# Flex_design.net
KiCad netlist of a schematic drawn in Altium Designer
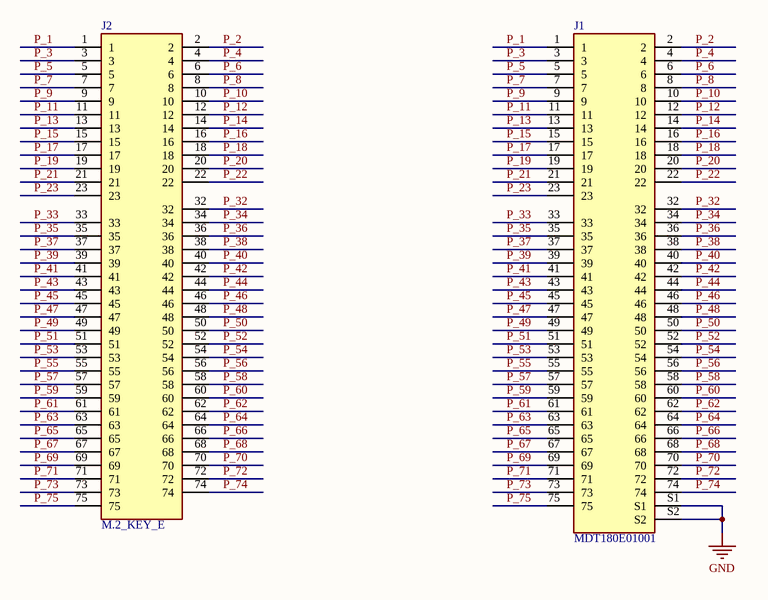
[diagram p0: Flex_design.SchDoc]

(export (version "E")
  (design (tool "Eeschema 10.0.6"))
  (components
    (comp (ref "J1")
      (value "MDT180E01001")
      (footprint "AMPHENOL_MDT180E01001")
      (description "PCIe M.2 Connectors, Storage and Server Connector, P=0.5mm, H=1.8mm, Key E, 30渭in Au Plating")
      (fields (field (name "MF") "Amphenol"))
      (libsource (lib "flex_Sch") (part "MDT180E01001"))
    )
    (comp (ref "J2")
      (value "M.2_KEY_E")
      (footprint "M.2_KEY_E")
      (libsource (lib "flex_Sch") (part "M.2_KEY_E"))
    )
  )
  (nets
    (net (code "1") (name "/P_1") (class "Default")
      (node (ref "J1") (pin "1") (pinfunction "1_1") (pintype "passive"))
      (node (ref "J2") (pin "1") (pinfunction "1_1") (pintype "passive"))
    )
    (net (code "2") (name "/P_2") (class "Default")
      (node (ref "J1") (pin "2") (pinfunction "2_2") (pintype "passive"))
      (node (ref "J2") (pin "2") (pinfunction "2_2") (pintype "passive"))
    )
    (net (code "3") (name "/P_3") (class "Default")
      (node (ref "J1") (pin "3") (pinfunction "3_3") (pintype "passive"))
      (node (ref "J2") (pin "3") (pinfunction "3_3") (pintype "passive"))
    )
    (net (code "4") (name "/P_4") (class "Default")
      (node (ref "J1") (pin "4") (pinfunction "4_4") (pintype "passive"))
      (node (ref "J2") (pin "4") (pinfunction "4_4") (pintype "passive"))
    )
    (net (code "5") (name "/P_5") (class "Default")
      (node (ref "J1") (pin "5") (pinfunction "5_5") (pintype "passive"))
      (node (ref "J2") (pin "5") (pinfunction "5_5") (pintype "passive"))
    )
    (net (code "6") (name "/P_6") (class "Default")
      (node (ref "J1") (pin "6") (pinfunction "6_6") (pintype "passive"))
      (node (ref "J2") (pin "6") (pinfunction "6_6") (pintype "passive"))
    )
    (net (code "7") (name "/P_7") (class "Default")
      (node (ref "J1") (pin "7") (pinfunction "7_7") (pintype "passive"))
      (node (ref "J2") (pin "7") (pinfunction "7_7") (pintype "passive"))
    )
    (net (code "8") (name "/P_8") (class "Default")
      (node (ref "J1") (pin "8") (pinfunction "8_8") (pintype "passive"))
      (node (ref "J2") (pin "8") (pinfunction "8_8") (pintype "passive"))
    )
    (net (code "9") (name "/P_9") (class "Default")
      (node (ref "J1") (pin "9") (pinfunction "9_9") (pintype "passive"))
      (node (ref "J2") (pin "9") (pinfunction "9_9") (pintype "passive"))
    )
    (net (code "10") (name "/P_10") (class "Default")
      (node (ref "J1") (pin "10") (pinfunction "10_10") (pintype "passive"))
      (node (ref "J2") (pin "10") (pinfunction "10_10") (pintype "passive"))
    )
    (net (code "11") (name "/P_11") (class "Default")
      (node (ref "J1") (pin "11") (pinfunction "11_11") (pintype "passive"))
      (node (ref "J2") (pin "11") (pinfunction "11_11") (pintype "passive"))
    )
    (net (code "12") (name "/P_12") (class "Default")
      (node (ref "J1") (pin "12") (pinfunction "12_12") (pintype "passive"))
      (node (ref "J2") (pin "12") (pinfunction "12_12") (pintype "passive"))
    )
    (net (code "13") (name "/P_13") (class "Default")
      (node (ref "J1") (pin "13") (pinfunction "13_13") (pintype "passive"))
      (node (ref "J2") (pin "13") (pinfunction "13_13") (pintype "passive"))
    )
    (net (code "14") (name "/P_14") (class "Default")
      (node (ref "J1") (pin "14") (pinfunction "14_14") (pintype "passive"))
      (node (ref "J2") (pin "14") (pinfunction "14_14") (pintype "passive"))
    )
    (net (code "15") (name "/P_15") (class "Default")
      (node (ref "J1") (pin "15") (pinfunction "15_15") (pintype "passive"))
      (node (ref "J2") (pin "15") (pinfunction "15_15") (pintype "passive"))
    )
    (net (code "16") (name "/P_16") (class "Default")
      (node (ref "J1") (pin "16") (pinfunction "16_16") (pintype "passive"))
      (node (ref "J2") (pin "16") (pinfunction "16_16") (pintype "passive"))
    )
    (net (code "17") (name "/P_17") (class "Default")
      (node (ref "J1") (pin "17") (pinfunction "17_17") (pintype "passive"))
      (node (ref "J2") (pin "17") (pinfunction "17_17") (pintype "passive"))
    )
    (net (code "18") (name "/P_18") (class "Default")
      (node (ref "J1") (pin "18") (pinfunction "18_18") (pintype "passive"))
      (node (ref "J2") (pin "18") (pinfunction "18_18") (pintype "passive"))
    )
    (net (code "19") (name "/P_19") (class "Default")
      (node (ref "J1") (pin "19") (pinfunction "19_19") (pintype "passive"))
      (node (ref "J2") (pin "19") (pinfunction "19_19") (pintype "passive"))
    )
    (net (code "20") (name "/P_20") (class "Default")
      (node (ref "J1") (pin "20") (pinfunction "20_20") (pintype "passive"))
      (node (ref "J2") (pin "20") (pinfunction "20_20") (pintype "passive"))
    )
    (net (code "21") (name "/P_21") (class "Default")
      (node (ref "J1") (pin "21") (pinfunction "21_21") (pintype "passive"))
      (node (ref "J2") (pin "21") (pinfunction "21_21") (pintype "passive"))
    )
    (net (code "22") (name "/P_22") (class "Default")
      (node (ref "J1") (pin "22") (pinfunction "22_22") (pintype "passive"))
      (node (ref "J2") (pin "22") (pinfunction "22_22") (pintype "passive"))
    )
    (net (code "23") (name "/P_23") (class "Default")
      (node (ref "J1") (pin "23") (pinfunction "23_23") (pintype "passive"))
      (node (ref "J2") (pin "23") (pinfunction "23_23") (pintype "passive"))
    )
    (net (code "24") (name "/P_32") (class "Default")
      (node (ref "J1") (pin "32") (pinfunction "32_32") (pintype "passive"))
      (node (ref "J2") (pin "32") (pinfunction "32_32") (pintype "passive"))
    )
    (net (code "25") (name "/P_33") (class "Default")
      (node (ref "J1") (pin "33") (pinfunction "33_33") (pintype "passive"))
      (node (ref "J2") (pin "33") (pinfunction "33_33") (pintype "passive"))
    )
    (net (code "26") (name "/P_34") (class "Default")
      (node (ref "J1") (pin "34") (pinfunction "34_34") (pintype "passive"))
      (node (ref "J2") (pin "34") (pinfunction "34_34") (pintype "passive"))
    )
    (net (code "27") (name "/P_35") (class "Default")
      (node (ref "J1") (pin "35") (pinfunction "35_35") (pintype "passive"))
      (node (ref "J2") (pin "35") (pinfunction "35_35") (pintype "passive"))
    )
    (net (code "28") (name "/P_36") (class "Default")
      (node (ref "J1") (pin "36") (pinfunction "36_36") (pintype "passive"))
      (node (ref "J2") (pin "36") (pinfunction "36_36") (pintype "passive"))
    )
    (net (code "29") (name "/P_37") (class "Default")
      (node (ref "J1") (pin "37") (pinfunction "37_37") (pintype "passive"))
      (node (ref "J2") (pin "37") (pinfunction "37_37") (pintype "passive"))
    )
    (net (code "30") (name "/P_38") (class "Default")
      (node (ref "J1") (pin "38") (pinfunction "38_38") (pintype "passive"))
      (node (ref "J2") (pin "38") (pinfunction "38_38") (pintype "passive"))
    )
    (net (code "31") (name "/P_39") (class "Default")
      (node (ref "J1") (pin "39") (pinfunction "39_39") (pintype "passive"))
      (node (ref "J2") (pin "39") (pinfunction "39_39") (pintype "passive"))
    )
    (net (code "32") (name "/P_40") (class "Default")
      (node (ref "J1") (pin "40") (pinfunction "40_40") (pintype "passive"))
      (node (ref "J2") (pin "40") (pinfunction "40_40") (pintype "passive"))
    )
    (net (code "33") (name "/P_41") (class "Default")
      (node (ref "J1") (pin "41") (pinfunction "41_41") (pintype "passive"))
      (node (ref "J2") (pin "41") (pinfunction "41_41") (pintype "passive"))
    )
    (net (code "34") (name "/P_42") (class "Default")
      (node (ref "J1") (pin "42") (pinfunction "42_42") (pintype "passive"))
      (node (ref "J2") (pin "42") (pinfunction "42_42") (pintype "passive"))
    )
    (net (code "35") (name "/P_43") (class "Default")
      (node (ref "J1") (pin "43") (pinfunction "43_43") (pintype "passive"))
      (node (ref "J2") (pin "43") (pinfunction "43_43") (pintype "passive"))
    )
    (net (code "36") (name "/P_44") (class "Default")
      (node (ref "J1") (pin "44") (pinfunction "44_44") (pintype "passive"))
      (node (ref "J2") (pin "44") (pinfunction "44_44") (pintype "passive"))
    )
    (net (code "37") (name "/P_45") (class "Default")
      (node (ref "J1") (pin "45") (pinfunction "45_45") (pintype "passive"))
      (node (ref "J2") (pin "45") (pinfunction "45_45") (pintype "passive"))
    )
    (net (code "38") (name "/P_46") (class "Default")
      (node (ref "J1") (pin "46") (pinfunction "46_46") (pintype "passive"))
      (node (ref "J2") (pin "46") (pinfunction "46_46") (pintype "passive"))
    )
    (net (code "39") (name "/P_47") (class "Default")
      (node (ref "J1") (pin "47") (pinfunction "47_47") (pintype "passive"))
      (node (ref "J2") (pin "47") (pinfunction "47_47") (pintype "passive"))
    )
    (net (code "40") (name "/P_48") (class "Default")
      (node (ref "J1") (pin "48") (pinfunction "48_48") (pintype "passive"))
      (node (ref "J2") (pin "48") (pinfunction "48_48") (pintype "passive"))
    )
    (net (code "41") (name "/P_49") (class "Default")
      (node (ref "J1") (pin "49") (pinfunction "49_49") (pintype "passive"))
      (node (ref "J2") (pin "49") (pinfunction "49_49") (pintype "passive"))
    )
    (net (code "42") (name "/P_50") (class "Default")
      (node (ref "J1") (pin "50") (pinfunction "50_50") (pintype "passive"))
      (node (ref "J2") (pin "50") (pinfunction "50_50") (pintype "passive"))
    )
    (net (code "43") (name "/P_51") (class "Default")
      (node (ref "J1") (pin "51") (pinfunction "51_51") (pintype "passive"))
      (node (ref "J2") (pin "51") (pinfunction "51_51") (pintype "passive"))
    )
    (net (code "44") (name "/P_52") (class "Default")
      (node (ref "J1") (pin "52") (pinfunction "52_52") (pintype "passive"))
      (node (ref "J2") (pin "52") (pinfunction "52_52") (pintype "passive"))
    )
    (net (code "45") (name "/P_53") (class "Default")
      (node (ref "J1") (pin "53") (pinfunction "53_53") (pintype "passive"))
      (node (ref "J2") (pin "53") (pinfunction "53_53") (pintype "passive"))
    )
    (net (code "46") (name "/P_54") (class "Default")
      (node (ref "J1") (pin "54") (pinfunction "54_54") (pintype "passive"))
      (node (ref "J2") (pin "54") (pinfunction "54_54") (pintype "passive"))
    )
    (net (code "47") (name "/P_55") (class "Default")
      (node (ref "J1") (pin "55") (pinfunction "55_55") (pintype "passive"))
      (node (ref "J2") (pin "55") (pinfunction "55_55") (pintype "passive"))
    )
    (net (code "48") (name "/P_56") (class "Default")
      (node (ref "J1") (pin "56") (pinfunction "56_56") (pintype "passive"))
      (node (ref "J2") (pin "56") (pinfunction "56_56") (pintype "passive"))
    )
    (net (code "49") (name "/P_57") (class "Default")
      (node (ref "J1") (pin "57") (pinfunction "57_57") (pintype "passive"))
      (node (ref "J2") (pin "57") (pinfunction "57_57") (pintype "passive"))
    )
    (net (code "50") (name "/P_58") (class "Default")
      (node (ref "J1") (pin "58") (pinfunction "58_58") (pintype "passive"))
      (node (ref "J2") (pin "58") (pinfunction "58_58") (pintype "passive"))
    )
    (net (code "51") (name "/P_59") (class "Default")
      (node (ref "J1") (pin "59") (pinfunction "59_59") (pintype "passive"))
      (node (ref "J2") (pin "59") (pinfunction "59_59") (pintype "passive"))
    )
    (net (code "52") (name "/P_60") (class "Default")
      (node (ref "J1") (pin "60") (pinfunction "60_60") (pintype "passive"))
      (node (ref "J2") (pin "60") (pinfunction "60_60") (pintype "passive"))
    )
    (net (code "53") (name "/P_61") (class "Default")
      (node (ref "J1") (pin "61") (pinfunction "61_61") (pintype "passive"))
      (node (ref "J2") (pin "61") (pinfunction "61_61") (pintype "passive"))
    )
    (net (code "54") (name "/P_62") (class "Default")
      (node (ref "J1") (pin "62") (pinfunction "62_62") (pintype "passive"))
      (node (ref "J2") (pin "62") (pinfunction "62_62") (pintype "passive"))
    )
    (net (code "55") (name "/P_63") (class "Default")
      (node (ref "J1") (pin "63") (pinfunction "63_63") (pintype "passive"))
      (node (ref "J2") (pin "63") (pinfunction "63_63") (pintype "passive"))
    )
    (net (code "56") (name "/P_64") (class "Default")
      (node (ref "J1") (pin "64") (pinfunction "64_64") (pintype "passive"))
      (node (ref "J2") (pin "64") (pinfunction "64_64") (pintype "passive"))
    )
    (net (code "57") (name "/P_65") (class "Default")
      (node (ref "J1") (pin "65") (pinfunction "65_65") (pintype "passive"))
      (node (ref "J2") (pin "65") (pinfunction "65_65") (pintype "passive"))
    )
    (net (code "58") (name "/P_66") (class "Default")
      (node (ref "J1") (pin "66") (pinfunction "66_66") (pintype "passive"))
      (node (ref "J2") (pin "66") (pinfunction "66_66") (pintype "passive"))
    )
    (net (code "59") (name "/P_67") (class "Default")
      (node (ref "J1") (pin "67") (pinfunction "67_67") (pintype "passive"))
      (node (ref "J2") (pin "67") (pinfunction "67_67") (pintype "passive"))
    )
    (net (code "60") (name "/P_68") (class "Default")
      (node (ref "J1") (pin "68") (pinfunction "68_68") (pintype "passive"))
      (node (ref "J2") (pin "68") (pinfunction "68_68") (pintype "passive"))
    )
    (net (code "61") (name "/P_69") (class "Default")
      (node (ref "J1") (pin "69") (pinfunction "69_69") (pintype "passive"))
      (node (ref "J2") (pin "69") (pinfunction "69_69") (pintype "passive"))
    )
    (net (code "62") (name "/P_70") (class "Default")
      (node (ref "J1") (pin "70") (pinfunction "70_70") (pintype "passive"))
      (node (ref "J2") (pin "70") (pinfunction "70_70") (pintype "passive"))
    )
    (net (code "63") (name "/P_71") (class "Default")
      (node (ref "J1") (pin "71") (pinfunction "71_71") (pintype "passive"))
      (node (ref "J2") (pin "71") (pinfunction "71_71") (pintype "passive"))
    )
    (net (code "64") (name "/P_72") (class "Default")
      (node (ref "J1") (pin "72") (pinfunction "72_72") (pintype "passive"))
      (node (ref "J2") (pin "72") (pinfunction "72_72") (pintype "passive"))
    )
    (net (code "65") (name "/P_73") (class "Default")
      (node (ref "J1") (pin "73") (pinfunction "73_73") (pintype "passive"))
      (node (ref "J2") (pin "73") (pinfunction "73_73") (pintype "passive"))
    )
    (net (code "66") (name "/P_74") (class "Default")
      (node (ref "J1") (pin "74") (pinfunction "74_74") (pintype "passive"))
      (node (ref "J2") (pin "74") (pinfunction "74_74") (pintype "passive"))
    )
    (net (code "67") (name "/P_75") (class "Default")
      (node (ref "J1") (pin "75") (pinfunction "75_75") (pintype "passive"))
      (node (ref "J2") (pin "75") (pinfunction "75_75") (pintype "passive"))
    )
    (net (code "68") (name "GND") (class "Default")
      (node (ref "J1") (pin "S1") (pinfunction "S1_S1") (pintype "passive"))
      (node (ref "J1") (pin "S2") (pinfunction "S2_S2") (pintype "passive"))
    )
  )
)
